# SD.net
KiCad netlist of a schematic drawn in Altium Designer
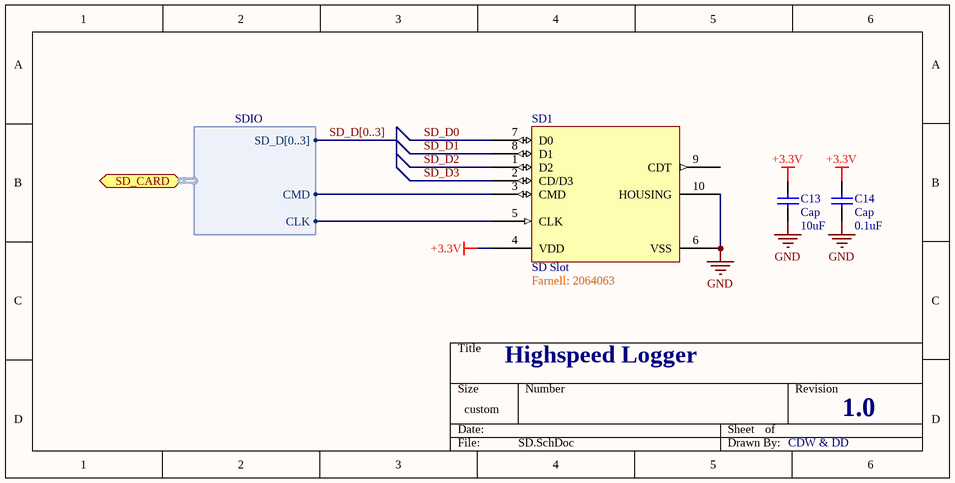
[diagram p0: SD.SchDoc]

(export (version "E")
  (design (tool "Eeschema 10.0.6"))
  (components
    (comp (ref "C13")
      (value "Cap")
      (footprint "V0603")
      (description "Capacitor")
      (fields (field (name "ALTIUM_VALUE") "10uF") (field (name "PUBLISHER") "Altium Limited"))
      (libsource (lib "Miscellaneous Devices") (part "Cap"))
    )
    (comp (ref "C14")
      (value "Cap")
      (footprint "V0402")
      (description "Capacitor")
      (fields (field (name "ALTIUM_VALUE") "0.1uF") (field (name "PUBLISHER") "Altium Limited"))
      (libsource (lib "Miscellaneous Devices") (part "Cap"))
    )
    (comp (ref "SD1")
      (value "SD Slot")
      (footprint "MICROSD-card")
      (fields (field (name "FARNELL") "2064063"))
      (libsource (lib "MiscComponents") (part "SD Slot"))
    )
  )
  (nets
    (net (code "2") (name "+3.3V") (class "Default")
      (node (ref "C13") (pin "1") (pinfunction "1_1") (pintype "passive"))
      (node (ref "C14") (pin "1") (pinfunction "1_1") (pintype "passive"))
      (node (ref "SD1") (pin "4") (pinfunction "VDD_4") (pintype "power_in"))
    )
    (net (code "3") (name "/CLK") (class "Default")
      (node (ref "SD1") (pin "5") (pinfunction "CLK_5") (pintype "input"))
    )
    (net (code "4") (name "/CMD") (class "Default")
      (node (ref "SD1") (pin "3") (pinfunction "CMD_3") (pintype "bidirectional"))
    )
    (net (code "5") (name "/SD_D0") (class "Default")
      (node (ref "SD1") (pin "7") (pinfunction "D0_7") (pintype "bidirectional"))
    )
    (net (code "6") (name "/SD_D1") (class "Default")
      (node (ref "SD1") (pin "8") (pinfunction "D1_8") (pintype "bidirectional"))
    )
    (net (code "7") (name "/SD_D2") (class "Default")
      (node (ref "SD1") (pin "1") (pinfunction "D2_1") (pintype "bidirectional"))
    )
    (net (code "8") (name "/SD_D3") (class "Default")
      (node (ref "SD1") (pin "2") (pinfunction "CD/D3_2") (pintype "bidirectional"))
    )
    (net (code "11") (name "GND") (class "Default")
      (node (ref "C13") (pin "2") (pinfunction "2_2") (pintype "passive"))
      (node (ref "C14") (pin "2") (pinfunction "2_2") (pintype "passive"))
      (node (ref "SD1") (pin "10") (pinfunction "HOUSING_10") (pintype "passive"))
      (node (ref "SD1") (pin "6") (pinfunction "VSS_6") (pintype "power_in"))
    )
    (net (code "12") (name "unconnected-(SD1-CDT-Pad9)") (class "Default")
      (node (ref "SD1") (pin "9") (pinfunction "CDT_9") (pintype "output"))
    )
  )
)
